# platform2.net
KiCad netlist of a schematic drawn in EAGLE
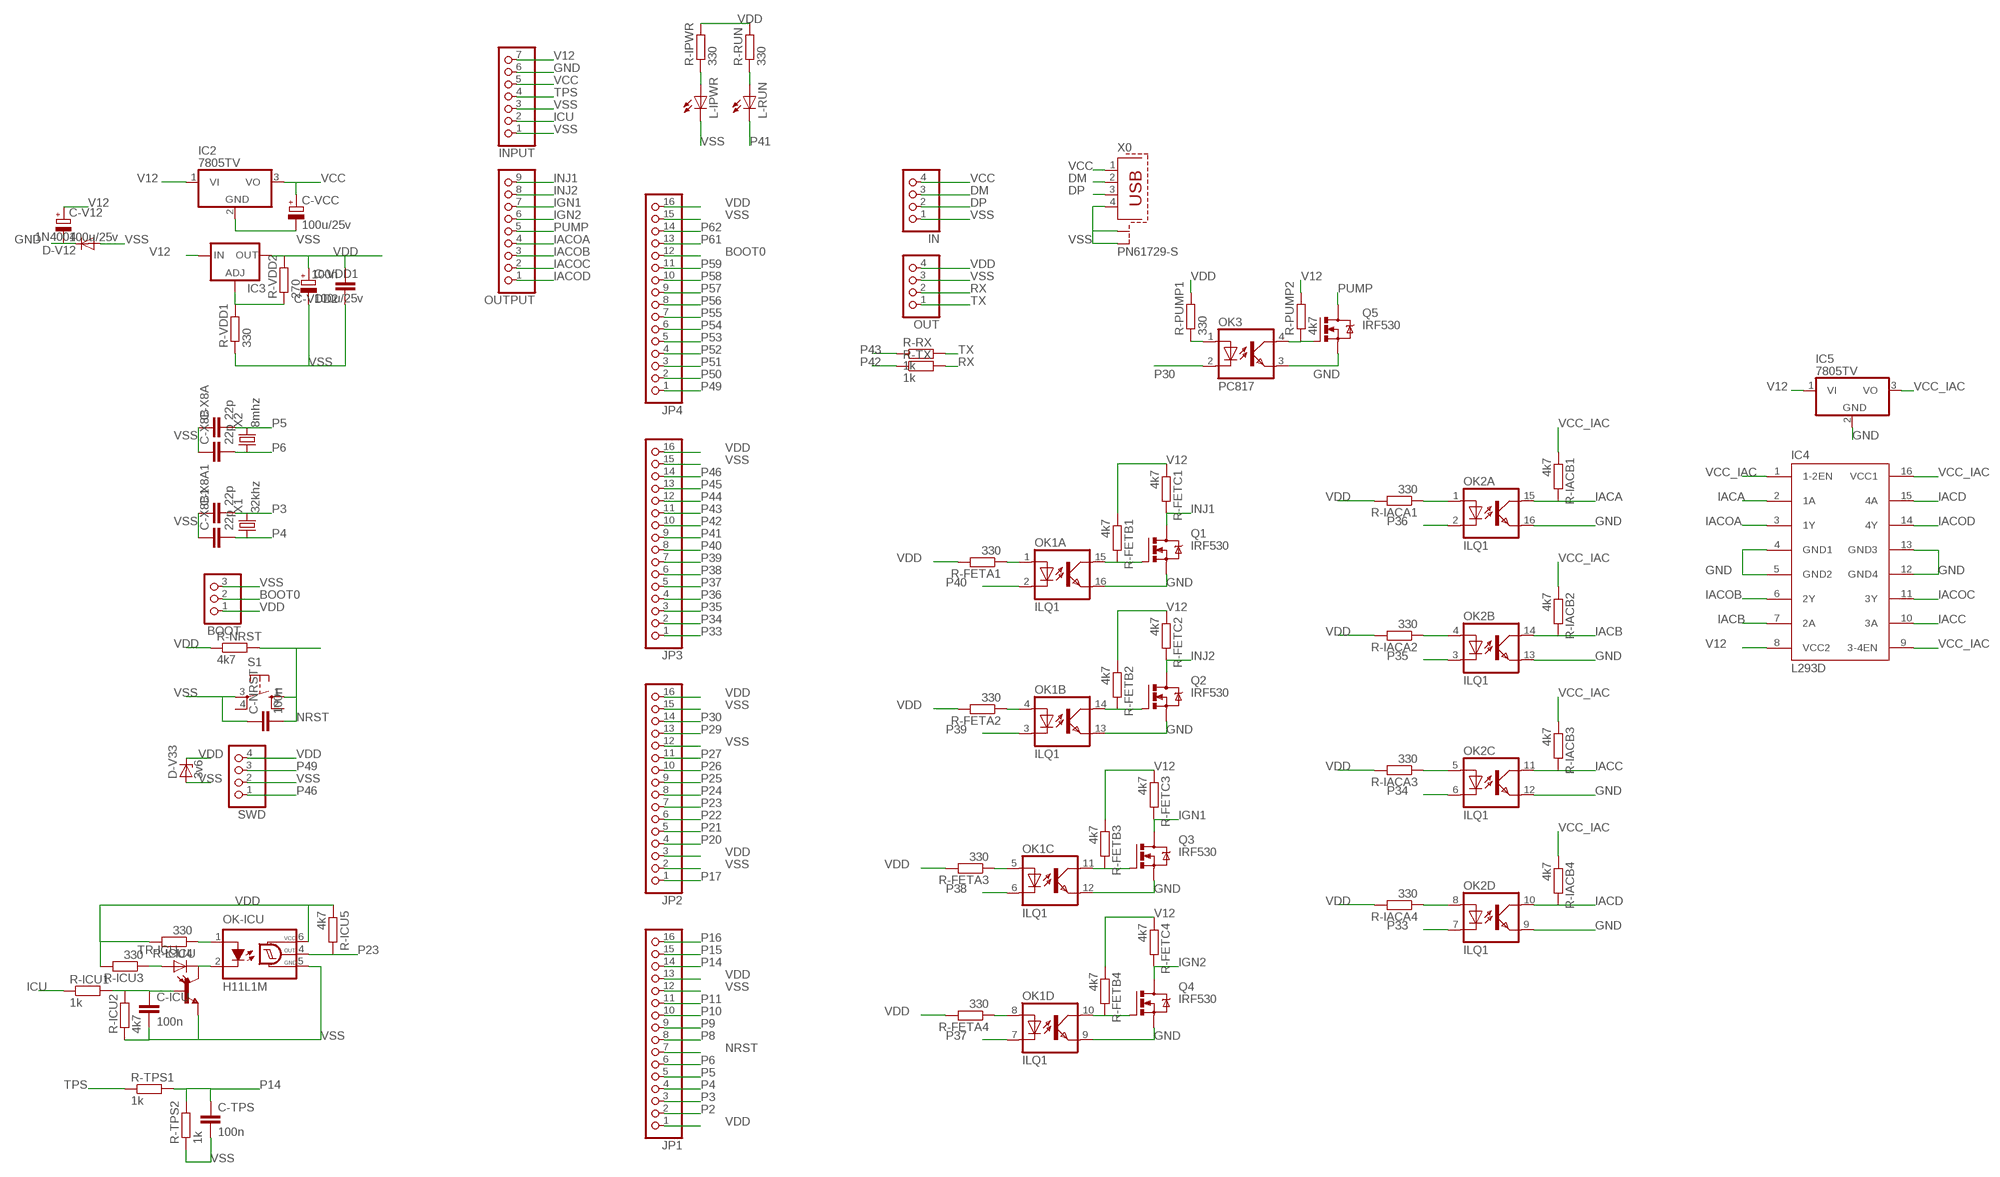
[diagram p0: schematic, sheet 1]

(export (version "E")
  (design (tool "Eeschema 10.0.6"))
  (components
    (comp (ref "BOOT")
      (value "PINHD-1X3")
      (footprint "eagle-import:1X03")
      (libsource (lib "eagle-import") (part "PINHD-1X3"))
    )
    (comp (ref "C-ICU")
      (value "100n")
      (footprint "eagle-import:C050-024X044")
      (libsource (lib "eagle-import") (part "C-EU050-024X044"))
    )
    (comp (ref "C-NRST")
      (value "100n")
      (footprint "eagle-import:C050-024X044")
      (libsource (lib "eagle-import") (part "C-EU050-024X044"))
    )
    (comp (ref "C-TPS")
      (value "100n")
      (footprint "eagle-import:C050-024X044")
      (libsource (lib "eagle-import") (part "C-EU050-024X044"))
    )
    (comp (ref "C-V12")
      (value "100u/25v")
      (footprint "eagle-import:E2-5")
      (libsource (lib "eagle-import") (part "CPOL-EUE2-5"))
    )
    (comp (ref "C-VCC")
      (value "100u/25v")
      (footprint "eagle-import:E2-5")
      (libsource (lib "eagle-import") (part "CPOL-EUE2-5"))
    )
    (comp (ref "C-VDD1")
      (value "100u/25v")
      (footprint "eagle-import:E2-5")
      (libsource (lib "eagle-import") (part "CPOL-EUE2-5"))
    )
    (comp (ref "C-VDD2")
      (value "100n")
      (footprint "eagle-import:C050-024X044")
      (libsource (lib "eagle-import") (part "C-EU050-024X044"))
    )
    (comp (ref "C-X8A")
      (value "22p")
      (footprint "eagle-import:C025-024X044")
      (libsource (lib "eagle-import") (part "C-EU025-024X044"))
    )
    (comp (ref "C-X8A1")
      (value "22p")
      (footprint "eagle-import:C025-024X044")
      (libsource (lib "eagle-import") (part "C-EU025-024X044"))
    )
    (comp (ref "C-X8B")
      (value "22p")
      (footprint "eagle-import:C025-024X044")
      (libsource (lib "eagle-import") (part "C-EU025-024X044"))
    )
    (comp (ref "C-X8B1")
      (value "22p")
      (footprint "eagle-import:C025-024X044")
      (libsource (lib "eagle-import") (part "C-EU025-024X044"))
    )
    (comp (ref "D-V12")
      (value "1N4004")
      (footprint "eagle-import:DO41-10")
      (libsource (lib "eagle-import") (part "1N4004"))
    )
    (comp (ref "D-V33")
      (value "3v6")
      (footprint "eagle-import:ZDIO-7.5")
      (libsource (lib "eagle-import") (part "ZENER-DIODEZD-7.5"))
    )
    (comp (ref "IC2")
      (value "7805TV")
      (footprint "eagle-import:TO220V")
      (libsource (lib "eagle-import") (part "78TV05"))
    )
    (comp (ref "IC3")
      (value "LM317TS")
      (footprint "eagle-import:317TS")
      (libsource (lib "eagle-import") (part "LM317TS"))
    )
    (comp (ref "IC4")
      (value "L293D")
      (footprint "eagle-import:DIL16")
      (libsource (lib "eagle-import") (part "L293D"))
    )
    (comp (ref "IC5")
      (value "7805TV")
      (footprint "eagle-import:TO220V")
      (libsource (lib "eagle-import") (part "78TV05"))
    )
    (comp (ref "IN")
      (value "PINHD-1X4")
      (footprint "eagle-import:1X04")
      (libsource (lib "eagle-import") (part "PINHD-1X4"))
    )
    (comp (ref "INPUT")
      (value "PINHD-1X7")
      (footprint "eagle-import:1X07")
      (libsource (lib "eagle-import") (part "PINHD-1X7"))
    )
    (comp (ref "JP1")
      (value "PINHD-1X16")
      (footprint "eagle-import:1X16")
      (libsource (lib "eagle-import") (part "PINHD-1X16"))
    )
    (comp (ref "JP2")
      (value "PINHD-1X16")
      (footprint "eagle-import:1X16")
      (libsource (lib "eagle-import") (part "PINHD-1X16"))
    )
    (comp (ref "JP3")
      (value "PINHD-1X16")
      (footprint "eagle-import:1X16")
      (libsource (lib "eagle-import") (part "PINHD-1X16"))
    )
    (comp (ref "JP4")
      (value "PINHD-1X16")
      (footprint "eagle-import:1X16")
      (libsource (lib "eagle-import") (part "PINHD-1X16"))
    )
    (comp (ref "L-ICU")
      (value "LED3MM")
      (footprint "eagle-import:LED3MM")
      (libsource (lib "eagle-import") (part "LED3MM"))
    )
    (comp (ref "L-IPWR")
      (value "LED3MM")
      (footprint "eagle-import:LED3MM")
      (libsource (lib "eagle-import") (part "LED3MM"))
    )
    (comp (ref "L-RUN")
      (value "LED3MM")
      (footprint "eagle-import:LED3MM")
      (libsource (lib "eagle-import") (part "LED3MM"))
    )
    (comp (ref "OK-ICU")
      (value "H11L1M")
      (footprint "eagle-import:DIL06")
      (fields (field (name "MF") "FAIRCHILD SEMICONDUCTOR") (field (name "MPN") "H11L1-M"))
      (libsource (lib "eagle-import") (part "H11LM1"))
    )
    (comp (ref "OK1")
      (value "ILQ1")
      (footprint "eagle-import:DIL16")
      (fields (field (name "MF") "VISHAY/TELEFUNKEN"))
      (libsource (lib "eagle-import") (part "ILQ1"))
    )
    (comp (ref "OK2")
      (value "ILQ1")
      (footprint "eagle-import:DIL16")
      (fields (field (name "MF") "VISHAY/TELEFUNKEN"))
      (libsource (lib "eagle-import") (part "ILQ1"))
    )
    (comp (ref "OK3")
      (value "PC817")
      (footprint "eagle-import:DIL04")
      (fields (field (name "MPN") "PC817X4J000F"))
      (libsource (lib "eagle-import") (part "PC817"))
    )
    (comp (ref "OUT")
      (value "PINHD-1X4")
      (footprint "eagle-import:1X04")
      (libsource (lib "eagle-import") (part "PINHD-1X4"))
    )
    (comp (ref "OUTPUT")
      (value "PINHD-1X9")
      (footprint "eagle-import:1X09")
      (libsource (lib "eagle-import") (part "PINHD-1X9"))
    )
    (comp (ref "Q1")
      (value "IRF530")
      (footprint "eagle-import:TO220BV")
      (libsource (lib "eagle-import") (part "IRF530"))
    )
    (comp (ref "Q2")
      (value "IRF530")
      (footprint "eagle-import:TO220BV")
      (libsource (lib "eagle-import") (part "IRF530"))
    )
    (comp (ref "Q3")
      (value "IRF530")
      (footprint "eagle-import:TO220BV")
      (libsource (lib "eagle-import") (part "IRF530"))
    )
    (comp (ref "Q4")
      (value "IRF530")
      (footprint "eagle-import:TO220BV")
      (libsource (lib "eagle-import") (part "IRF530"))
    )
    (comp (ref "Q5")
      (value "IRF530")
      (footprint "eagle-import:TO220BV")
      (libsource (lib "eagle-import") (part "IRF530"))
    )
    (comp (ref "R-FETA1")
      (value "330")
      (footprint "eagle-import:0204_7")
      (libsource (lib "eagle-import") (part "R-EU_0204/7"))
    )
    (comp (ref "R-FETA2")
      (value "330")
      (footprint "eagle-import:0204_7")
      (libsource (lib "eagle-import") (part "R-EU_0204/7"))
    )
    (comp (ref "R-FETA3")
      (value "330")
      (footprint "eagle-import:0204_7")
      (libsource (lib "eagle-import") (part "R-EU_0204/7"))
    )
    (comp (ref "R-FETA4")
      (value "330")
      (footprint "eagle-import:0204_7")
      (libsource (lib "eagle-import") (part "R-EU_0204/7"))
    )
    (comp (ref "R-FETB1")
      (value "4k7")
      (footprint "eagle-import:0204_7")
      (libsource (lib "eagle-import") (part "R-EU_0204/7"))
    )
    (comp (ref "R-FETB2")
      (value "4k7")
      (footprint "eagle-import:0204_7")
      (libsource (lib "eagle-import") (part "R-EU_0204/7"))
    )
    (comp (ref "R-FETB3")
      (value "4k7")
      (footprint "eagle-import:0204_7")
      (libsource (lib "eagle-import") (part "R-EU_0204/7"))
    )
    (comp (ref "R-FETB4")
      (value "4k7")
      (footprint "eagle-import:0204_7")
      (libsource (lib "eagle-import") (part "R-EU_0204/7"))
    )
    (comp (ref "R-FETC1")
      (value "4k7")
      (footprint "eagle-import:0204_7")
      (libsource (lib "eagle-import") (part "R-EU_0204/7"))
    )
    (comp (ref "R-FETC2")
      (value "4k7")
      (footprint "eagle-import:0204_7")
      (libsource (lib "eagle-import") (part "R-EU_0204/7"))
    )
    (comp (ref "R-FETC3")
      (value "4k7")
      (footprint "eagle-import:0204_7")
      (libsource (lib "eagle-import") (part "R-EU_0204/7"))
    )
    (comp (ref "R-FETC4")
      (value "4k7")
      (footprint "eagle-import:0204_7")
      (libsource (lib "eagle-import") (part "R-EU_0204/7"))
    )
    (comp (ref "R-IACA1")
      (value "330")
      (footprint "eagle-import:0204_7")
      (libsource (lib "eagle-import") (part "R-EU_0204/7"))
    )
    (comp (ref "R-IACA2")
      (value "330")
      (footprint "eagle-import:0204_7")
      (libsource (lib "eagle-import") (part "R-EU_0204/7"))
    )
    (comp (ref "R-IACA3")
      (value "330")
      (footprint "eagle-import:0204_7")
      (libsource (lib "eagle-import") (part "R-EU_0204/7"))
    )
    (comp (ref "R-IACA4")
      (value "330")
      (footprint "eagle-import:0204_7")
      (libsource (lib "eagle-import") (part "R-EU_0204/7"))
    )
    (comp (ref "R-IACB1")
      (value "4k7")
      (footprint "eagle-import:0204_7")
      (libsource (lib "eagle-import") (part "R-EU_0204/7"))
    )
    (comp (ref "R-IACB2")
      (value "4k7")
      (footprint "eagle-import:0204_7")
      (libsource (lib "eagle-import") (part "R-EU_0204/7"))
    )
    (comp (ref "R-IACB3")
      (value "4k7")
      (footprint "eagle-import:0204_7")
      (libsource (lib "eagle-import") (part "R-EU_0204/7"))
    )
    (comp (ref "R-IACB4")
      (value "4k7")
      (footprint "eagle-import:0204_7")
      (libsource (lib "eagle-import") (part "R-EU_0204/7"))
    )
    (comp (ref "R-ICU1")
      (value "1k")
      (footprint "eagle-import:0204_7")
      (libsource (lib "eagle-import") (part "R-EU_0204/7"))
    )
    (comp (ref "R-ICU2")
      (value "4k7")
      (footprint "eagle-import:0204_7")
      (libsource (lib "eagle-import") (part "R-EU_0204/7"))
    )
    (comp (ref "R-ICU3")
      (value "330")
      (footprint "eagle-import:0204_7")
      (libsource (lib "eagle-import") (part "R-EU_0204/7"))
    )
    (comp (ref "R-ICU4")
      (value "330")
      (footprint "eagle-import:0204_7")
      (libsource (lib "eagle-import") (part "R-EU_0204/7"))
    )
    (comp (ref "R-ICU5")
      (value "4k7")
      (footprint "eagle-import:0204_7")
      (libsource (lib "eagle-import") (part "R-EU_0204/7"))
    )
    (comp (ref "R-IPWR")
      (value "330")
      (footprint "eagle-import:0204_7")
      (libsource (lib "eagle-import") (part "R-EU_0204/7"))
    )
    (comp (ref "R-NRST")
      (value "4k7")
      (footprint "eagle-import:0204_7")
      (libsource (lib "eagle-import") (part "R-EU_0204/7"))
    )
    (comp (ref "R-PUMP1")
      (value "330")
      (footprint "eagle-import:0204_7")
      (libsource (lib "eagle-import") (part "R-EU_0204/7"))
    )
    (comp (ref "R-PUMP2")
      (value "4k7")
      (footprint "eagle-import:0204_7")
      (libsource (lib "eagle-import") (part "R-EU_0204/7"))
    )
    (comp (ref "R-RUN")
      (value "330")
      (footprint "eagle-import:0204_7")
      (libsource (lib "eagle-import") (part "R-EU_0204/7"))
    )
    (comp (ref "R-RX")
      (value "1k")
      (footprint "eagle-import:0204_7")
      (libsource (lib "eagle-import") (part "R-EU_0204/7"))
    )
    (comp (ref "R-TPS1")
      (value "1k")
      (footprint "eagle-import:0204_7")
      (libsource (lib "eagle-import") (part "R-EU_0204/7"))
    )
    (comp (ref "R-TPS2")
      (value "1k")
      (footprint "eagle-import:0204_7")
      (libsource (lib "eagle-import") (part "R-EU_0204/7"))
    )
    (comp (ref "R-TX")
      (value "1k")
      (footprint "eagle-import:0204_7")
      (libsource (lib "eagle-import") (part "R-EU_0204/7"))
    )
    (comp (ref "R-VDD1")
      (value "330")
      (footprint "eagle-import:0204_7")
      (libsource (lib "eagle-import") (part "R-EU_0204/7"))
    )
    (comp (ref "R-VDD2")
      (value "270")
      (footprint "eagle-import:0204_7")
      (libsource (lib "eagle-import") (part "R-EU_0204/7"))
    )
    (comp (ref "S1")
      (value "10-XX")
      (footprint "eagle-import:B3F-10XX")
      (fields (field (name "MPN") "B3F-1000"))
      (libsource (lib "eagle-import") (part "10-XX"))
    )
    (comp (ref "SWD")
      (value "PINHD-1X4")
      (footprint "eagle-import:1X04")
      (libsource (lib "eagle-import") (part "PINHD-1X4"))
    )
    (comp (ref "TR-ICU")
      (value "2N3904-NPN-TO92-EBC")
      (footprint "eagle-import:TO92-EBC")
      (libsource (lib "eagle-import") (part "-NPN-TO92-EBC2N3904"))
    )
    (comp (ref "X0")
      (value "PN61729-S")
      (footprint "eagle-import:PN61729-S")
      (libsource (lib "eagle-import") (part "PN61729-S"))
    )
    (comp (ref "X1")
      (value "32khz")
      (footprint "eagle-import:TC26V")
      (libsource (lib "eagle-import") (part "CRYSTALTC26V"))
    )
    (comp (ref "X2")
      (value "8mhz")
      (footprint "eagle-import:HC49U-V")
      (libsource (lib "eagle-import") (part "CRYSTALHC49U-V"))
    )
  )
  (nets
    (net (code "1") (name "/BOOT0") (class "Default")
      (node (ref "BOOT") (pin "2") (pinfunction "2_2") (pintype "passive"))
      (node (ref "JP4") (pin "12") (pinfunction "12_12") (pintype "passive"))
    )
    (net (code "2") (name "/DM") (class "Default")
      (node (ref "IN") (pin "3") (pinfunction "3_3") (pintype "passive"))
      (node (ref "X0") (pin "2") (pinfunction "2_2") (pintype "passive"))
    )
    (net (code "3") (name "/DP") (class "Default")
      (node (ref "IN") (pin "2") (pinfunction "2_2") (pintype "passive"))
      (node (ref "X0") (pin "3") (pinfunction "3_3") (pintype "passive"))
    )
    (net (code "4") (name "/GND") (class "Default")
      (node (ref "C-V12") (pin "-") (pinfunction "-_-") (pintype "passive"))
      (node (ref "D-V12") (pin "C") (pinfunction "C_C") (pintype "passive"))
      (node (ref "IC4") (pin "12") (pinfunction "GND4_12") (pintype "power_in"))
      (node (ref "IC4") (pin "13") (pinfunction "GND3_13") (pintype "power_in"))
      (node (ref "IC4") (pin "4") (pinfunction "GND1_4") (pintype "power_in"))
      (node (ref "IC4") (pin "5") (pinfunction "GND2_5") (pintype "power_in"))
      (node (ref "IC5") (pin "2") (pinfunction "GND_2") (pintype "passive"))
      (node (ref "INPUT") (pin "6") (pinfunction "6_6") (pintype "passive"))
      (node (ref "OK1") (pin "12") (pinfunction "EMIT_12") (pintype "passive"))
      (node (ref "OK1") (pin "13") (pinfunction "EMIT_13") (pintype "passive"))
      (node (ref "OK1") (pin "16") (pinfunction "EMIT_16") (pintype "passive"))
      (node (ref "OK1") (pin "9") (pinfunction "EMIT_9") (pintype "passive"))
      (node (ref "OK2") (pin "12") (pinfunction "EMIT_12") (pintype "passive"))
      (node (ref "OK2") (pin "13") (pinfunction "EMIT_13") (pintype "passive"))
      (node (ref "OK2") (pin "16") (pinfunction "EMIT_16") (pintype "passive"))
      (node (ref "OK2") (pin "9") (pinfunction "EMIT_9") (pintype "passive"))
      (node (ref "OK3") (pin "3") (pinfunction "EMIT_3") (pintype "passive"))
      (node (ref "Q1") (pin "S") (pinfunction "S_S") (pintype "passive"))
      (node (ref "Q2") (pin "S") (pinfunction "S_S") (pintype "passive"))
      (node (ref "Q3") (pin "S") (pinfunction "S_S") (pintype "passive"))
      (node (ref "Q4") (pin "S") (pinfunction "S_S") (pintype "passive"))
      (node (ref "Q5") (pin "S") (pinfunction "S_S") (pintype "passive"))
    )
    (net (code "5") (name "/IACA") (class "Default")
      (node (ref "IC4") (pin "2") (pinfunction "1A_2") (pintype "input"))
      (node (ref "OK2") (pin "15") (pinfunction "COL_15") (pintype "passive"))
      (node (ref "R-IACB1") (pin "2") (pinfunction "2_2") (pintype "passive"))
    )
    (net (code "6") (name "/IACB") (class "Default")
      (node (ref "IC4") (pin "7") (pinfunction "2A_7") (pintype "input"))
      (node (ref "OK2") (pin "14") (pinfunction "COL_14") (pintype "passive"))
      (node (ref "R-IACB2") (pin "2") (pinfunction "2_2") (pintype "passive"))
    )
    (net (code "7") (name "/IACC") (class "Default")
      (node (ref "IC4") (pin "10") (pinfunction "3A_10") (pintype "input"))
      (node (ref "OK2") (pin "11") (pinfunction "COL_11") (pintype "passive"))
      (node (ref "R-IACB3") (pin "2") (pinfunction "2_2") (pintype "passive"))
    )
    (net (code "8") (name "/IACD") (class "Default")
      (node (ref "IC4") (pin "15") (pinfunction "4A_15") (pintype "input"))
      (node (ref "OK2") (pin "10") (pinfunction "COL_10") (pintype "passive"))
      (node (ref "R-IACB4") (pin "2") (pinfunction "2_2") (pintype "passive"))
    )
    (net (code "9") (name "/IACOA") (class "Default")
      (node (ref "IC4") (pin "3") (pinfunction "1Y_3") (pintype "output"))
      (node (ref "OUTPUT") (pin "4") (pinfunction "4_4") (pintype "passive"))
    )
    (net (code "10") (name "/IACOB") (class "Default")
      (node (ref "IC4") (pin "6") (pinfunction "2Y_6") (pintype "output"))
      (node (ref "OUTPUT") (pin "3") (pinfunction "3_3") (pintype "passive"))
    )
    (net (code "11") (name "/IACOC") (class "Default")
      (node (ref "IC4") (pin "11") (pinfunction "3Y_11") (pintype "output"))
      (node (ref "OUTPUT") (pin "2") (pinfunction "2_2") (pintype "passive"))
    )
    (net (code "12") (name "/IACOD") (class "Default")
      (node (ref "IC4") (pin "14") (pinfunction "4Y_14") (pintype "output"))
      (node (ref "OUTPUT") (pin "1") (pinfunction "1_1") (pintype "passive"))
    )
    (net (code "13") (name "/ICU") (class "Default")
      (node (ref "INPUT") (pin "2") (pinfunction "2_2") (pintype "passive"))
      (node (ref "R-ICU1") (pin "1") (pinfunction "1_1") (pintype "passive"))
    )
    (net (code "14") (name "/IGN1") (class "Default")
      (node (ref "OUTPUT") (pin "7") (pinfunction "7_7") (pintype "passive"))
      (node (ref "Q3") (pin "D") (pinfunction "D_D") (pintype "passive"))
      (node (ref "R-FETC3") (pin "2") (pinfunction "2_2") (pintype "passive"))
    )
    (net (code "15") (name "/IGN2") (class "Default")
      (node (ref "OUTPUT") (pin "6") (pinfunction "6_6") (pintype "passive"))
      (node (ref "Q4") (pin "D") (pinfunction "D_D") (pintype "passive"))
      (node (ref "R-FETC4") (pin "2") (pinfunction "2_2") (pintype "passive"))
    )
    (net (code "16") (name "/INJ1") (class "Default")
      (node (ref "OUTPUT") (pin "9") (pinfunction "9_9") (pintype "passive"))
      (node (ref "Q1") (pin "D") (pinfunction "D_D") (pintype "passive"))
      (node (ref "R-FETC1") (pin "2") (pinfunction "2_2") (pintype "passive"))
    )
    (net (code "17") (name "/INJ2") (class "Default")
      (node (ref "OUTPUT") (pin "8") (pinfunction "8_8") (pintype "passive"))
      (node (ref "Q2") (pin "D") (pinfunction "D_D") (pintype "passive"))
      (node (ref "R-FETC2") (pin "2") (pinfunction "2_2") (pintype "passive"))
    )
    (net (code "18") (name "/NRST") (class "Default")
      (node (ref "C-NRST") (pin "2") (pinfunction "2_2") (pintype "passive"))
      (node (ref "JP1") (pin "7") (pinfunction "7_7") (pintype "passive"))
      (node (ref "R-NRST") (pin "2") (pinfunction "2_2") (pintype "passive"))
      (node (ref "S1") (pin "1") (pinfunction "S_1") (pintype "passive"))
    )
    (net (code "19") (name "/P2") (class "Default")
      (node (ref "JP1") (pin "2") (pinfunction "2_2") (pintype "passive"))
    )
    (net (code "20") (name "/P3") (class "Default")
      (node (ref "C-X8A1") (pin "2") (pinfunction "2_2") (pintype "passive"))
      (node (ref "JP1") (pin "3") (pinfunction "3_3") (pintype "passive"))
      (node (ref "X1") (pin "2") (pinfunction "2_2") (pintype "passive"))
    )
    (net (code "21") (name "/P4") (class "Default")
      (node (ref "C-X8B1") (pin "2") (pinfunction "2_2") (pintype "passive"))
      (node (ref "JP1") (pin "4") (pinfunction "4_4") (pintype "passive"))
      (node (ref "X1") (pin "1") (pinfunction "1_1") (pintype "passive"))
    )
    (net (code "22") (name "/P5") (class "Default")
      (node (ref "C-X8A") (pin "2") (pinfunction "2_2") (pintype "passive"))
      (node (ref "JP1") (pin "5") (pinfunction "5_5") (pintype "passive"))
      (node (ref "X2") (pin "2") (pinfunction "2_2") (pintype "passive"))
    )
    (net (code "23") (name "/P6") (class "Default")
      (node (ref "C-X8B") (pin "2") (pinfunction "2_2") (pintype "passive"))
      (node (ref "JP1") (pin "6") (pinfunction "6_6") (pintype "passive"))
      (node (ref "X2") (pin "1") (pinfunction "1_1") (pintype "passive"))
    )
    (net (code "24") (name "/P8") (class "Default")
      (node (ref "JP1") (pin "8") (pinfunction "8_8") (pintype "passive"))
    )
    (net (code "25") (name "/P9") (class "Default")
      (node (ref "JP1") (pin "9") (pinfunction "9_9") (pintype "passive"))
    )
    (net (code "26") (name "/P10") (class "Default")
      (node (ref "JP1") (pin "10") (pinfunction "10_10") (pintype "passive"))
    )
    (net (code "27") (name "/P11") (class "Default")
      (node (ref "JP1") (pin "11") (pinfunction "11_11") (pintype "passive"))
    )
    (net (code "28") (name "/P14") (class "Default")
      (node (ref "C-TPS") (pin "1") (pinfunction "1_1") (pintype "passive"))
      (node (ref "JP1") (pin "14") (pinfunction "14_14") (pintype "passive"))
      (node (ref "R-TPS1") (pin "2") (pinfunction "2_2") (pintype "passive"))
      (node (ref "R-TPS2") (pin "2") (pinfunction "2_2") (pintype "passive"))
    )
    (net (code "29") (name "/P15") (class "Default")
      (node (ref "JP1") (pin "15") (pinfunction "15_15") (pintype "passive"))
    )
    (net (code "30") (name "/P16") (class "Default")
      (node (ref "JP1") (pin "16") (pinfunction "16_16") (pintype "passive"))
    )
    (net (code "31") (name "/P17") (class "Default")
      (node (ref "JP2") (pin "1") (pinfunction "1_1") (pintype "passive"))
    )
    (net (code "32") (name "/P20") (class "Default")
      (node (ref "JP2") (pin "4") (pinfunction "4_4") (pintype "passive"))
    )
    (net (code "33") (name "/P21") (class "Default")
      (node (ref "JP2") (pin "5") (pinfunction "5_5") (pintype "passive"))
    )
    (net (code "34") (name "/P22") (class "Default")
      (node (ref "JP2") (pin "6") (pinfunction "6_6") (pintype "passive"))
    )
    (net (code "35") (name "/P23") (class "Default")
      (node (ref "JP2") (pin "7") (pinfunction "7_7") (pintype "passive"))
      (node (ref "OK-ICU") (pin "4") (pinfunction "OUT_4") (pintype "output"))
      (node (ref "R-ICU5") (pin "2") (pinfunction "2_2") (pintype "passive"))
    )
    (net (code "36") (name "/P24") (class "Default")
      (node (ref "JP2") (pin "8") (pinfunction "8_8") (pintype "passive"))
    )
    (net (code "37") (name "/P25") (class "Default")
      (node (ref "JP2") (pin "9") (pinfunction "9_9") (pintype "passive"))
    )
    (net (code "38") (name "/P26") (class "Default")
      (node (ref "JP2") (pin "10") (pinfunction "10_10") (pintype "passive"))
    )
    (net (code "39") (name "/P27") (class "Default")
      (node (ref "JP2") (pin "11") (pinfunction "11_11") (pintype "passive"))
    )
    (net (code "40") (name "/P29") (class "Default")
      (node (ref "JP2") (pin "13") (pinfunction "13_13") (pintype "passive"))
    )
    (net (code "41") (name "/P30") (class "Default")
      (node (ref "JP2") (pin "14") (pinfunction "14_14") (pintype "passive"))
      (node (ref "OK3") (pin "2") (pinfunction "C_2") (pintype "passive"))
    )
    (net (code "42") (name "/P33") (class "Default")
      (node (ref "JP3") (pin "1") (pinfunction "1_1") (pintype "passive"))
      (node (ref "OK2") (pin "7") (pinfunction "C_7") (pintype "passive"))
    )
    (net (code "43") (name "/P34") (class "Default")
      (node (ref "JP3") (pin "2") (pinfunction "2_2") (pintype "passive"))
      (node (ref "OK2") (pin "6") (pinfunction "C_6") (pintype "passive"))
    )
    (net (code "44") (name "/P35") (class "Default")
      (node (ref "JP3") (pin "3") (pinfunction "3_3") (pintype "passive"))
      (node (ref "OK2") (pin "3") (pinfunction "C_3") (pintype "passive"))
    )
    (net (code "45") (name "/P36") (class "Default")
      (node (ref "JP3") (pin "4") (pinfunction "4_4") (pintype "passive"))
      (node (ref "OK2") (pin "2") (pinfunction "C_2") (pintype "passive"))
    )
    (net (code "46") (name "/P37") (class "Default")
      (node (ref "JP3") (pin "5") (pinfunction "5_5") (pintype "passive"))
      (node (ref "OK1") (pin "7") (pinfunction "C_7") (pintype "passive"))
    )
    (net (code "47") (name "/P38") (class "Default")
      (node (ref "JP3") (pin "6") (pinfunction "6_6") (pintype "passive"))
      (node (ref "OK1") (pin "6") (pinfunction "C_6") (pintype "passive"))
    )
    (net (code "48") (name "/P39") (class "Default")
      (node (ref "JP3") (pin "7") (pinfunction "7_7") (pintype "passive"))
      (node (ref "OK1") (pin "3") (pinfunction "C_3") (pintype "passive"))
    )
    (net (code "49") (name "/P40") (class "Default")
      (node (ref "JP3") (pin "8") (pinfunction "8_8") (pintype "passive"))
      (node (ref "OK1") (pin "2") (pinfunction "C_2") (pintype "passive"))
    )
    (net (code "50") (name "/P41") (class "Default")
      (node (ref "JP3") (pin "9") (pinfunction "9_9") (pintype "passive"))
      (node (ref "L-RUN") (pin "K") (pinfunction "C_K") (pintype "passive"))
    )
    (net (code "51") (name "/P42") (class "Default")
      (node (ref "JP3") (pin "10") (pinfunction "10_10") (pintype "passive"))
      (node (ref "R-TX") (pin "1") (pinfunction "1_1") (pintype "passive"))
    )
    (net (code "52") (name "/P43") (class "Default")
      (node (ref "JP3") (pin "11") (pinfunction "11_11") (pintype "passive"))
      (node (ref "R-RX") (pin "1") (pinfunction "1_1") (pintype "passive"))
    )
    (net (code "53") (name "/P44") (class "Default")
      (node (ref "JP3") (pin "12") (pinfunction "12_12") (pintype "passive"))
    )
    (net (code "54") (name "/P45") (class "Default")
      (node (ref "JP3") (pin "13") (pinfunction "13_13") (pintype "passive"))
    )
    (net (code "55") (name "/P46") (class "Default")
      (node (ref "JP3") (pin "14") (pinfunction "14_14") (pintype "passive"))
      (node (ref "SWD") (pin "1") (pinfunction "1_1") (pintype "passive"))
    )
    (net (code "56") (name "/P49") (class "Default")
      (node (ref "JP4") (pin "1") (pinfunction "1_1") (pintype "passive"))
      (node (ref "SWD") (pin "3") (pinfunction "3_3") (pintype "passive"))
    )
    (net (code "57") (name "/P50") (class "Default")
      (node (ref "JP4") (pin "2") (pinfunction "2_2") (pintype "passive"))
    )
    (net (code "58") (name "/P51") (class "Default")
      (node (ref "JP4") (pin "3") (pinfunction "3_3") (pintype "passive"))
    )
    (net (code "59") (name "/P52") (class "Default")
      (node (ref "JP4") (pin "4") (pinfunction "4_4") (pintype "passive"))
    )
    (net (code "60") (name "/P53") (class "Default")
      (node (ref "JP4") (pin "5") (pinfunction "5_5") (pintype "passive"))
    )
    (net (code "61") (name "/P54") (class "Default")
      (node (ref "JP4") (pin "6") (pinfunction "6_6") (pintype "passive"))
    )
    (net (code "62") (name "/P55") (class "Default")
      (node (ref "JP4") (pin "7") (pinfunction "7_7") (pintype "passive"))
    )
    (net (code "63") (name "/P56") (class "Default")
      (node (ref "JP4") (pin "8") (pinfunction "8_8") (pintype "passive"))
    )
    (net (code "64") (name "/P57") (class "Default")
      (node (ref "JP4") (pin "9") (pinfunction "9_9") (pintype "passive"))
    )
    (net (code "65") (name "/P58") (class "Default")
      (node (ref "JP4") (pin "10") (pinfunction "10_10") (pintype "passive"))
    )
    (net (code "66") (name "/P59") (class "Default")
      (node (ref "JP4") (pin "11") (pinfunction "11_11") (pintype "passive"))
    )
    (net (code "67") (name "/P61") (class "Default")
      (node (ref "JP4") (pin "13") (pinfunction "13_13") (pintype "passive"))
    )
    (net (code "68") (name "/P62") (class "Default")
      (node (ref "JP4") (pin "14") (pinfunction "14_14") (pintype "passive"))
    )
    (net (code "69") (name "/PUMP") (class "Default")
      (node (ref "OUTPUT") (pin "5") (pinfunction "5_5") (pintype "passive"))
      (node (ref "Q5") (pin "D") (pinfunction "D_D") (pintype "passive"))
    )
    (net (code "70") (name "/RX") (class "Default")
      (node (ref "OUT") (pin "2") (pinfunction "2_2") (pintype "passive"))
      (node (ref "R-TX") (pin "2") (pinfunction "2_2") (pintype "passive"))
    )
    (net (code "71") (name "/TPS") (class "Default")
      (node (ref "INPUT") (pin "4") (pinfunction "4_4") (pintype "passive"))
      (node (ref "R-TPS1") (pin "1") (pinfunction "1_1") (pintype "passive"))
    )
    (net (code "72") (name "/TX") (class "Default")
      (node (ref "OUT") (pin "1") (pinfunction "1_1") (pintype "passive"))
      (node (ref "R-RX") (pin "2") (pinfunction "2_2") (pintype "passive"))
    )
    (net (code "73") (name "/V12") (class "Default")
      (node (ref "C-V12") (pin "+") (pinfunction "+_+") (pintype "passive"))
      (node (ref "IC2") (pin "1") (pinfunction "VI_1") (pintype "input"))
      (node (ref "IC3") (pin "3") (pinfunction "IN_3") (pintype "input"))
      (node (ref "IC4") (pin "8") (pinfunction "VCC2_8") (pintype "power_in"))
      (node (ref "IC5") (pin "1") (pinfunction "VI_1") (pintype "input"))
      (node (ref "INPUT") (pin "7") (pinfunction "7_7") (pintype "passive"))
      (node (ref "R-FETB1") (pin "1") (pinfunction "1_1") (pintype "passive"))
      (node (ref "R-FETB2") (pin "1") (pinfunction "1_1") (pintype "passive"))
      (node (ref "R-FETB3") (pin "1") (pinfunction "1_1") (pintype "passive"))
      (node (ref "R-FETB4") (pin "1") (pinfunction "1_1") (pintype "passive"))
      (node (ref "R-FETC1") (pin "1") (pinfunction "1_1") (pintype "passive"))
      (node (ref "R-FETC2") (pin "1") (pinfunction "1_1") (pintype "passive"))
      (node (ref "R-FETC3") (pin "1") (pinfunction "1_1") (pintype "passive"))
      (node (ref "R-FETC4") (pin "1") (pinfunction "1_1") (pintype "passive"))
      (node (ref "R-PUMP2") (pin "2") (pinfunction "2_2") (pintype "passive"))
    )
    (net (code "74") (name "/VCC") (class "Default")
      (node (ref "C-VCC") (pin "+") (pinfunction "+_+") (pintype "passive"))
      (node (ref "IC2") (pin "3") (pinfunction "VO_3") (pintype "passive"))
      (node (ref "IN") (pin "4") (pinfunction "4_4") (pintype "passive"))
      (node (ref "INPUT") (pin "5") (pinfunction "5_5") (pintype "passive"))
      (node (ref "X0") (pin "1") (pinfunction "1_1") (pintype "passive"))
    )
    (net (code "75") (name "/VCC_IAC") (class "Default")
      (node (ref "IC4") (pin "1") (pinfunction "1-2EN_1") (pintype "input"))
      (node (ref "IC4") (pin "16") (pinfunction "VCC1_16") (pintype "power_in"))
      (node (ref "IC4") (pin "9") (pinfunction "3-4EN_9") (pintype "input"))
      (node (ref "IC5") (pin "3") (pinfunction "VO_3") (pintype "passive"))
      (node (ref "R-IACB1") (pin "1") (pinfunction "1_1") (pintype "passive"))
      (node (ref "R-IACB2") (pin "1") (pinfunction "1_1") (pintype "passive"))
      (node (ref "R-IACB3") (pin "1") (pinfunction "1_1") (pintype "passive"))
      (node (ref "R-IACB4") (pin "1") (pinfunction "1_1") (pintype "passive"))
    )
    (net (code "76") (name "/VDD") (class "Default")
      (node (ref "BOOT") (pin "1") (pinfunction "1_1") (pintype "passive"))
      (node (ref "C-VDD1") (pin "+") (pinfunction "+_+") (pintype "passive"))
      (node (ref "C-VDD2") (pin "2") (pinfunction "2_2") (pintype "passive"))
      (node (ref "D-V33") (pin "C") (pinfunction "C_C") (pintype "passive"))
      (node (ref "IC3") (pin "2") (pinfunction "OUT_2") (pintype "passive"))
      (node (ref "JP1") (pin "1") (pinfunction "1_1") (pintype "passive"))
      (node (ref "JP1") (pin "13") (pinfunction "13_13") (pintype "passive"))
      (node (ref "JP2") (pin "16") (pinfunction "16_16") (pintype "passive"))
      (node (ref "JP2") (pin "3") (pinfunction "3_3") (pintype "passive"))
      (node (ref "JP3") (pin "16") (pinfunction "16_16") (pintype "passive"))
      (node (ref "JP4") (pin "16") (pinfunction "16_16") (pintype "passive"))
      (node (ref "OK-ICU") (pin "6") (pinfunction "VCC_6") (pintype "power_in"))
      (node (ref "OUT") (pin "4") (pinfunction "4_4") (pintype "passive"))
      (node (ref "R-FETA1") (pin "2") (pinfunction "2_2") (pintype "passive"))
      (node (ref "R-FETA2") (pin "2") (pinfunction "2_2") (pintype "passive"))
      (node (ref "R-FETA3") (pin "2") (pinfunction "2_2") (pintype "passive"))
      (node (ref "R-FETA4") (pin "2") (pinfunction "2_2") (pintype "passive"))
      (node (ref "R-IACA1") (pin "2") (pinfunction "2_2") (pintype "passive"))
      (node (ref "R-IACA2") (pin "2") (pinfunction "2_2") (pintype "passive"))
      (node (ref "R-IACA3") (pin "2") (pinfunction "2_2") (pintype "passive"))
      (node (ref "R-IACA4") (pin "2") (pinfunction "2_2") (pintype "passive"))
      (node (ref "R-ICU3") (pin "2") (pinfunction "2_2") (pintype "passive"))
      (node (ref "R-ICU4") (pin "2") (pinfunction "2_2") (pintype "passive"))
      (node (ref "R-ICU5") (pin "1") (pinfunction "1_1") (pintype "passive"))
      (node (ref "R-IPWR") (pin "2") (pinfunction "2_2") (pintype "passive"))
      (node (ref "R-NRST") (pin "1") (pinfunction "1_1") (pintype "passive"))
      (node (ref "R-PUMP1") (pin "2") (pinfunction "2_2") (pintype "passive"))
      (node (ref "R-RUN") (pin "2") (pinfunction "2_2") (pintype "passive"))
      (node (ref "R-VDD2") (pin "2") (pinfunction "2_2") (pintype "passive"))
      (node (ref "SWD") (pin "4") (pinfunction "4_4") (pintype "passive"))
    )
    (net (code "77") (name "/VSS") (class "Default")
      (node (ref "BOOT") (pin "3") (pinfunction "3_3") (pintype "passive"))
      (node (ref "C-ICU") (pin "2") (pinfunction "2_2") (pintype "passive"))
      (node (ref "C-NRST") (pin "1") (pinfunction "1_1") (pintype "passive"))
      (node (ref "C-TPS") (pin "2") (pinfunction "2_2") (pintype "passive"))
      (node (ref "C-VCC") (pin "-") (pinfunction "-_-") (pintype "passive"))
      (node (ref "C-VDD1") (pin "-") (pinfunction "-_-") (pintype "passive"))
      (node (ref "C-VDD2") (pin "1") (pinfunction "1_1") (pintype "passive"))
      (node (ref "C-X8A") (pin "1") (pinfunction "1_1") (pintype "passive"))
      (node (ref "C-X8A1") (pin "1") (pinfunction "1_1") (pintype "passive"))
      (node (ref "C-X8B") (pin "1") (pinfunction "1_1") (pintype "passive"))
      (node (ref "C-X8B1") (pin "1") (pinfunction "1_1") (pintype "passive"))
      (node (ref "D-V12") (pin "A") (pinfunction "A_A") (pintype "passive"))
      (node (ref "D-V33") (pin "A") (pinfunction "A_A") (pintype "passive"))
      (node (ref "IC2") (pin "2") (pinfunction "GND_2") (pintype "passive"))
      (node (ref "IN") (pin "1") (pinfunction "1_1") (pintype "passive"))
      (node (ref "INPUT") (pin "1") (pinfunction "1_1") (pintype "passive"))
      (node (ref "INPUT") (pin "3") (pinfunction "3_3") (pintype "passive"))
      (node (ref "JP1") (pin "12") (pinfunction "12_12") (pintype "passive"))
      (node (ref "JP2") (pin "12") (pinfunction "12_12") (pintype "passive"))
      (node (ref "JP2") (pin "15") (pinfunction "15_15") (pintype "passive"))
      (node (ref "JP2") (pin "2") (pinfunction "2_2") (pintype "passive"))
      (node (ref "JP3") (pin "15") (pinfunction "15_15") (pintype "passive"))
      (node (ref "JP4") (pin "15") (pinfunction "15_15") (pintype "passive"))
      (node (ref "L-IPWR") (pin "K") (pinfunction "C_K") (pintype "passive"))
      (node (ref "OK-ICU") (pin "5") (pinfunction "GND_5") (pintype "power_in"))
      (node (ref "OUT") (pin "3") (pinfunction "3_3") (pintype "passive"))
      (node (ref "R-ICU2") (pin "1") (pinfunction "1_1") (pintype "passive"))
      (node (ref "R-TPS2") (pin "1") (pinfunction "1_1") (pintype "passive"))
      (node (ref "R-VDD1") (pin "1") (pinfunction "1_1") (pintype "passive"))
      (node (ref "S1") (pin "3") (pinfunction "P_3") (pintype "passive"))
      (node (ref "SWD") (pin "2") (pinfunction "2_2") (pintype "passive"))
      (node (ref "TR-ICU") (pin "E") (pinfunction "E_E") (pintype "passive"))
      (node (ref "X0") (pin "4") (pinfunction "4_4") (pintype "passive"))
      (node (ref "X0") (pin "S1") (pinfunction "S1_S1") (pintype "passive"))
      (node (ref "X0") (pin "S2") (pinfunction "S2_S2") (pintype "passive"))
    )
    (net (code "78") (name "Net-(C-ICU-Pad1)") (class "Default")
      (node (ref "C-ICU") (pin "1") (pinfunction "1_1") (pintype "passive"))
      (node (ref "R-ICU1") (pin "2") (pinfunction "2_2") (pintype "passive"))
      (node (ref "R-ICU2") (pin "2") (pinfunction "2_2") (pintype "passive"))
      (node (ref "TR-ICU") (pin "B") (pinfunction "B_B") (pintype "passive"))
    )
    (net (code "79") (name "Net-(IC3-ADJ)") (class "Default")
      (node (ref "IC3") (pin "1") (pinfunction "ADJ_1") (pintype "input"))
      (node (ref "R-VDD1") (pin "2") (pinfunction "2_2") (pintype "passive"))
      (node (ref "R-VDD2") (pin "1") (pinfunction "1_1") (pintype "passive"))
    )
    (net (code "80") (name "Net-(L-ICU-C)") (class "Default")
      (node (ref "L-ICU") (pin "K") (pinfunction "C_K") (pintype "passive"))
      (node (ref "OK-ICU") (pin "2") (pinfunction "C_2") (pintype "passive"))
      (node (ref "TR-ICU") (pin "C") (pinfunction "C_C") (pintype "passive"))
    )
    (net (code "81") (name "Net-(L-ICU-PadA)") (class "Default")
      (node (ref "L-ICU") (pin "A") (pinfunction "A_A") (pintype "passive"))
      (node (ref "R-ICU3") (pin "1") (pinfunction "1_1") (pintype "passive"))
    )
    (net (code "82") (name "Net-(L-IPWR-PadA)") (class "Default")
      (node (ref "L-IPWR") (pin "A") (pinfunction "A_A") (pintype "passive"))
      (node (ref "R-IPWR") (pin "1") (pinfunction "1_1") (pintype "passive"))
    )
    (net (code "83") (name "Net-(L-RUN-PadA)") (class "Default")
      (node (ref "L-RUN") (pin "A") (pinfunction "A_A") (pintype "passive"))
      (node (ref "R-RUN") (pin "1") (pinfunction "1_1") (pintype "passive"))
    )
    (net (code "84") (name "Net-(OK-ICU-A)") (class "Default")
      (node (ref "OK-ICU") (pin "1") (pinfunction "A_1") (pintype "passive"))
      (node (ref "R-ICU4") (pin "1") (pinfunction "1_1") (pintype "passive"))
    )
    (net (code "85") (name "Net-(OK1A-A)") (class "Default")
      (node (ref "OK1") (pin "1") (pinfunction "A_1") (pintype "passive"))
      (node (ref "R-FETA1") (pin "1") (pinfunction "1_1") (pintype "passive"))
    )
    (net (code "86") (name "Net-(OK1A-COL)") (class "Default")
      (node (ref "OK1") (pin "15") (pinfunction "COL_15") (pintype "passive"))
      (node (ref "Q1") (pin "G") (pinfunction "G_G") (pintype "passive"))
      (node (ref "R-FETB1") (pin "2") (pinfunction "2_2") (pintype "passive"))
    )
    (net (code "87") (name "Net-(OK1B-A)") (class "Default")
      (node (ref "OK1") (pin "4") (pinfunction "A_4") (pintype "passive"))
      (node (ref "R-FETA2") (pin "1") (pinfunction "1_1") (pintype "passive"))
    )
    (net (code "88") (name "Net-(OK1B-COL)") (class "Default")
      (node (ref "OK1") (pin "14") (pinfunction "COL_14") (pintype "passive"))
      (node (ref "Q2") (pin "G") (pinfunction "G_G") (pintype "passive"))
      (node (ref "R-FETB2") (pin "2") (pinfunction "2_2") (pintype "passive"))
    )
    (net (code "89") (name "Net-(OK1C-A)") (class "Default")
      (node (ref "OK1") (pin "5") (pinfunction "A_5") (pintype "passive"))
      (node (ref "R-FETA3") (pin "1") (pinfunction "1_1") (pintype "passive"))
    )
    (net (code "90") (name "Net-(OK1C-COL)") (class "Default")
      (node (ref "OK1") (pin "11") (pinfunction "COL_11") (pintype "passive"))
      (node (ref "Q3") (pin "G") (pinfunction "G_G") (pintype "passive"))
      (node (ref "R-FETB3") (pin "2") (pinfunction "2_2") (pintype "passive"))
    )
    (net (code "91") (name "Net-(OK1D-A)") (class "Default")
      (node (ref "OK1") (pin "8") (pinfunction "A_8") (pintype "passive"))
      (node (ref "R-FETA4") (pin "1") (pinfunction "1_1") (pintype "passive"))
    )
    (net (code "92") (name "Net-(OK1D-COL)") (class "Default")
      (node (ref "OK1") (pin "10") (pinfunction "COL_10") (pintype "passive"))
      (node (ref "Q4") (pin "G") (pinfunction "G_G") (pintype "passive"))
      (node (ref "R-FETB4") (pin "2") (pinfunction "2_2") (pintype "passive"))
    )
    (net (code "93") (name "Net-(OK2A-A)") (class "Default")
      (node (ref "OK2") (pin "1") (pinfunction "A_1") (pintype "passive"))
      (node (ref "R-IACA1") (pin "1") (pinfunction "1_1") (pintype "passive"))
    )
    (net (code "94") (name "Net-(OK2B-A)") (class "Default")
      (node (ref "OK2") (pin "4") (pinfunction "A_4") (pintype "passive"))
      (node (ref "R-IACA2") (pin "1") (pinfunction "1_1") (pintype "passive"))
    )
    (net (code "95") (name "Net-(OK2C-A)") (class "Default")
      (node (ref "OK2") (pin "5") (pinfunction "A_5") (pintype "passive"))
      (node (ref "R-IACA3") (pin "1") (pinfunction "1_1") (pintype "passive"))
    )
    (net (code "96") (name "Net-(OK2D-A)") (class "Default")
      (node (ref "OK2") (pin "8") (pinfunction "A_8") (pintype "passive"))
      (node (ref "R-IACA4") (pin "1") (pinfunction "1_1") (pintype "passive"))
    )
    (net (code "97") (name "Net-(OK3-A)") (class "Default")
      (node (ref "OK3") (pin "1") (pinfunction "A_1") (pintype "passive"))
      (node (ref "R-PUMP1") (pin "1") (pinfunction "1_1") (pintype "passive"))
    )
    (net (code "98") (name "Net-(OK3-COL)") (class "Default")
      (node (ref "OK3") (pin "4") (pinfunction "COL_4") (pintype "passive"))
      (node (ref "Q5") (pin "G") (pinfunction "G_G") (pintype "passive"))
      (node (ref "R-PUMP2") (pin "1") (pinfunction "1_1") (pintype "passive"))
    )
    (net (code "99") (name "unconnected-(S1-P1-Pad4)") (class "Default")
      (node (ref "S1") (pin "4") (pinfunction "P1_4") (pintype "passive"))
    )
    (net (code "100") (name "unconnected-(S1-S1-Pad2)") (class "Default")
      (node (ref "S1") (pin "2") (pinfunction "S1_2") (pintype "passive"))
    )
  )
)
